# analog_channel3.net
KiCad netlist of a schematic drawn in Altium Designer
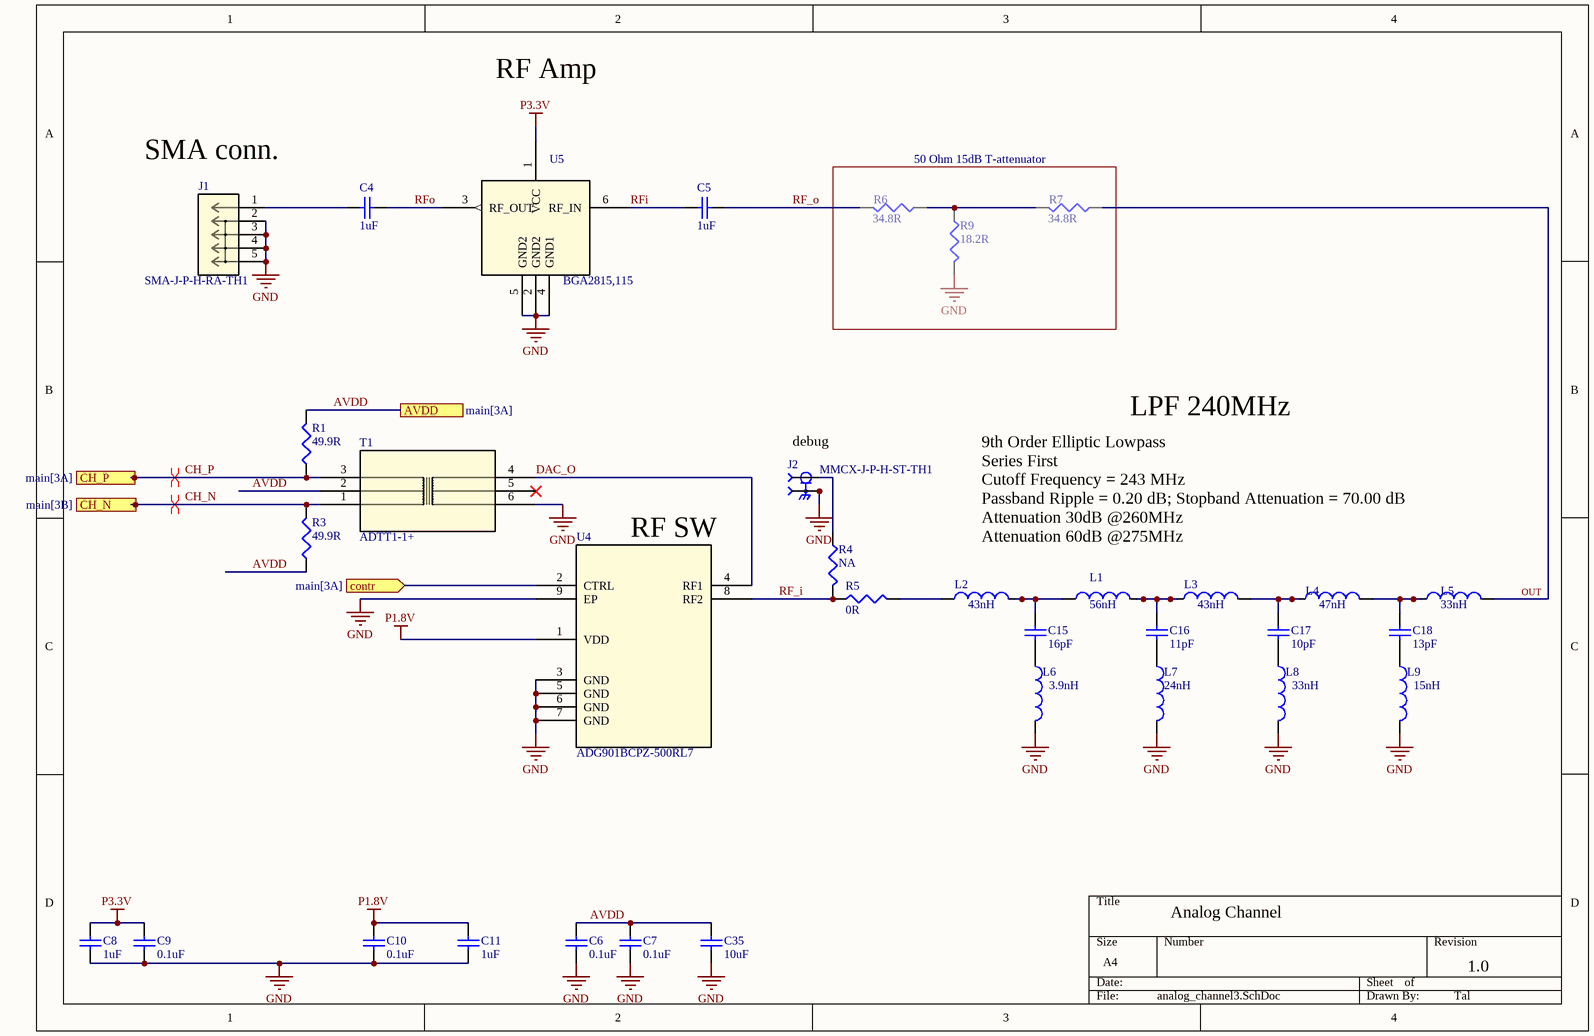
[diagram p0: analog_channel3.SchDoc]

(export (version "E")
  (design (tool "Eeschema 10.0.6"))
  (components
    (comp (ref "C4")
      (value "1uF 25V")
      (footprint "Landa_PCB:C0402")
      (description "CAP CER 1uF 25V X5R 0402")
      (fields
        (field (name "MANUFACTURER PART NUMBER") "C1005C0G1H6R8D")
        (field (name "MANUFACTURER") "TDK Corporation")
        (field (name "CAPACITANCE") "1uF")
      )
      (libsource (lib "L_SCH_C") (part "CAP CER 6.8pF 50V NP0 0402"))
    )
    (comp (ref "C5")
      (value "1uF 25V")
      (footprint "Landa_PCB:C0402")
      (description "CAP CER 1uF 25V X5R 0402")
      (fields
        (field (name "MANUFACTURER PART NUMBER") "C1005C0G1H6R8D")
        (field (name "MANUFACTURER") "TDK Corporation")
        (field (name "CAPACITANCE") "1uF")
      )
      (libsource (lib "L_SCH_C") (part "CAP CER 6.8pF 50V NP0 0402"))
    )
    (comp (ref "C6")
      (value "0.1uF 50V")
      (footprint "Landa_PCB:C0402")
      (description "CAP CER 0.1uF 50V NP0 0402")
      (fields
        (field (name "MANUFACTURER PART NUMBER") "C1005C0G1H6R8D")
        (field (name "MANUFACTURER") "TDK Corporation")
        (field (name "CAPACITANCE") "0.1uF")
      )
      (libsource (lib "L_SCH_C") (part "CAP CER 6.8pF 50V NP0 0402"))
    )
    (comp (ref "C7")
      (value "0.1uF 50V")
      (footprint "Landa_PCB:C0402")
      (description "CAP CER 0.1uF 50V NP0 0402")
      (fields
        (field (name "MANUFACTURER PART NUMBER") "C1005C0G1H6R8D")
        (field (name "MANUFACTURER") "TDK Corporation")
        (field (name "CAPACITANCE") "0.1uF")
      )
      (libsource (lib "L_SCH_C") (part "CAP CER 6.8pF 50V NP0 0402"))
    )
    (comp (ref "C8")
      (value "1uF 25V")
      (footprint "Landa_PCB:C0402")
      (description "CAP CER 1uF 25V X5R 0402")
      (fields
        (field (name "MANUFACTURER PART NUMBER") "C1005C0G1H6R8D")
        (field (name "MANUFACTURER") "TDK Corporation")
        (field (name "CAPACITANCE") "1uF")
      )
      (libsource (lib "L_SCH_C") (part "CAP CER 6.8pF 50V NP0 0402"))
    )
    (comp (ref "C9")
      (value "0.1uF 50V")
      (footprint "Landa_PCB:C0402")
      (description "CAP CER 0.1uF 50V NP0 0402")
      (fields
        (field (name "MANUFACTURER PART NUMBER") "C1005C0G1H6R8D")
        (field (name "MANUFACTURER") "TDK Corporation")
        (field (name "CAPACITANCE") "0.1uF")
      )
      (libsource (lib "L_SCH_C") (part "CAP CER 6.8pF 50V NP0 0402"))
    )
    (comp (ref "C10")
      (value "0.1uF 50V")
      (footprint "Landa_PCB:C0402")
      (description "CAP CER 0.1uF 50V NP0 0402")
      (fields
        (field (name "MANUFACTURER PART NUMBER") "C1005C0G1H6R8D")
        (field (name "MANUFACTURER") "TDK Corporation")
        (field (name "CAPACITANCE") "0.1uF")
      )
      (libsource (lib "L_SCH_C") (part "CAP CER 6.8pF 50V NP0 0402"))
    )
    (comp (ref "C11")
      (value "1uF 25V")
      (footprint "Landa_PCB:C0402")
      (description "CAP CER 1uF 25V X5R 0402")
      (fields
        (field (name "MANUFACTURER PART NUMBER") "C1005C0G1H6R8D")
        (field (name "MANUFACTURER") "TDK Corporation")
        (field (name "CAPACITANCE") "1uF")
      )
      (libsource (lib "L_SCH_C") (part "CAP CER 6.8pF 50V NP0 0402"))
    )
    (comp (ref "C15")
      (value "16pF 50V")
      (footprint "Landa_PCB:C0402")
      (description "CAP CER 16PF 50V 5% NP0 0402")
      (fields
        (field (name "MANUFACTURER") "TDK Corporation")
        (field (name "MANUFACTURER PART NUMBER") "C1005C0G1H200J")
        (field (name "CAPACITANCE") "16pF")
      )
      (libsource (lib "L_SCH_C") (part "CAP CER 20pF 50V 5% NP0 0402"))
    )
    (comp (ref "C16")
      (value "11pF 50V")
      (footprint "Landa_PCB:C0402")
      (description "CAP CER 11PF 50V 5% NP0 0402")
      (fields
        (field (name "MANUFACTURER") "TDK Corporation")
        (field (name "MANUFACTURER PART NUMBER") "C1005C0G1H200J")
        (field (name "CAPACITANCE") "11pF")
      )
      (libsource (lib "L_SCH_C") (part "CAP CER 20pF 50V 5% NP0 0402"))
    )
    (comp (ref "C17")
      (value "10pF 50V")
      (footprint "Landa_PCB:C0402")
      (description "CAP CER 10PF 50V 5% NP0 0402")
      (fields
        (field (name "MANUFACTURER") "TDK Corporation")
        (field (name "MANUFACTURER PART NUMBER") "C1005C0G1H200J")
        (field (name "CAPACITANCE") "10pF")
      )
      (libsource (lib "L_SCH_C") (part "CAP CER 20pF 50V 5% NP0 0402"))
    )
    (comp (ref "C18")
      (value "13pF 50V")
      (footprint "Landa_PCB:C0402")
      (description "CAP CER 13PF 50V 5% NP0 0402")
      (fields
        (field (name "MANUFACTURER") "TDK Corporation")
        (field (name "MANUFACTURER PART NUMBER") "C1005C0G1H200J")
        (field (name "CAPACITANCE") "13pF")
      )
      (libsource (lib "L_SCH_C") (part "CAP CER 20pF 50V 5% NP0 0402"))
    )
    (comp (ref "C35")
      (value "10uF 10V")
      (footprint "Landa_PCB:C0402")
      (description "CAP CER 10uF 10V X5R 0402")
      (fields
        (field (name "MANUFACTURER PART NUMBER") "C1005C0G1H6R8D")
        (field (name "MANUFACTURER") "TDK Corporation")
        (field (name "CAPACITANCE") "10uF")
      )
      (libsource (lib "L_SCH_C") (part "CAP CER 6.8pF 50V NP0 0402"))
    )
    (comp (ref "J1")
      (value "SMA-J-P-H-RA-TH1")
      (footprint "CONN_SMA-J-P-H-RA-TH1_SAI")
      (description "No Description Available")
      (fields (field (name "COPYRIGHT") "Copyright (C) 2023 Ultra Librarian. All rights reserved."))
      (libsource (lib "SMA-J-P-H-RA-TH1") (part "SMA-J-P-H-RA-TH1"))
    )
    (comp (ref "J2")
      (value "MMCX-J-P-H-ST-TH1")
      (footprint "SAMTEC_MMCX-J-P-H-ST-TH1")
      (description "MMCX STRAIGHT, THROUGH HOLE JACK- 50 OHM")
      (fields (field (name "MF") "Samtec"))
      (libsource (lib "MMCX-J-P-H-ST-TH1") (part "MMCX-J-P-H-ST-TH1"))
    )
    (comp (ref "L1")
      (value "56nH")
      (footprint "0402-A")
      (description "Inductor")
      (fields (field (name "PUBLISHER") "Altium Limited"))
      (libsource (lib "Miscellaneous Devices") (part "Inductor"))
    )
    (comp (ref "L2")
      (value "43nH")
      (footprint "0402-A")
      (description "Inductor")
      (fields (field (name "PUBLISHER") "Altium Limited"))
      (libsource (lib "Miscellaneous Devices") (part "Inductor"))
    )
    (comp (ref "L3")
      (value "43nH")
      (footprint "0402-A")
      (description "Inductor")
      (fields (field (name "PUBLISHER") "Altium Limited"))
      (libsource (lib "Miscellaneous Devices") (part "Inductor"))
    )
    (comp (ref "L4")
      (value "47nH")
      (footprint "0402-A")
      (description "Inductor")
      (fields (field (name "PUBLISHER") "Altium Limited"))
      (libsource (lib "Miscellaneous Devices") (part "Inductor"))
    )
    (comp (ref "L5")
      (value "33nH")
      (footprint "0402-A")
      (description "Inductor")
      (fields (field (name "PUBLISHER") "Altium Limited"))
      (libsource (lib "Miscellaneous Devices") (part "Inductor"))
    )
    (comp (ref "L6")
      (value "3.9nH")
      (footprint "0402-A")
      (description "Inductor")
      (fields (field (name "PUBLISHER") "Altium Limited"))
      (libsource (lib "Miscellaneous Devices") (part "Inductor"))
    )
    (comp (ref "L7")
      (value "24nH")
      (footprint "0402-A")
      (description "Inductor")
      (fields (field (name "PUBLISHER") "Altium Limited"))
      (libsource (lib "Miscellaneous Devices") (part "Inductor"))
    )
    (comp (ref "L8")
      (value "33nH")
      (footprint "0402-A")
      (description "Inductor")
      (fields (field (name "PUBLISHER") "Altium Limited"))
      (libsource (lib "Miscellaneous Devices") (part "Inductor"))
    )
    (comp (ref "L9")
      (value "15nH")
      (footprint "0402-A")
      (description "Inductor")
      (fields (field (name "PUBLISHER") "Altium Limited"))
      (libsource (lib "Miscellaneous Devices") (part "Inductor"))
    )
    (comp (ref "R1")
      (value "49.9R")
      (footprint "Landa_PCB:R0402")
      (description "RES 49.9 OHM 1/10W 1% 0402 SMD")
      (fields
        (field (name "MANUFACTURER PART NUMBER") "ERJ-2RKF1000X")
        (field (name "MANUFACTURER") "Panasonic Electronic Components")
      )
      (libsource (lib "L_SCH_R") (part "RES 100 OHM 1/10W 1% 0402 SMD"))
    )
    (comp (ref "R3")
      (value "49.9R")
      (footprint "Landa_PCB:R0402")
      (description "RES 49.9 OHM 1/10W 1% 0402 SMD")
      (fields
        (field (name "MANUFACTURER PART NUMBER") "ERJ-2RKF1000X")
        (field (name "MANUFACTURER") "Panasonic Electronic Components")
      )
      (libsource (lib "L_SCH_R") (part "RES 100 OHM 1/10W 1% 0402 SMD"))
    )
    (comp (ref "R4")
      (value "NA")
      (footprint "r0402")
      (description "RES 0 OHM 1/10W 1% 0402 SMD")
      (fields
        (field (name "MANUFACTURER PART NUMBER") "ERJ-2RKF1000X")
        (field (name "MANUFACTURER") "Panasonic Electronic Components")
      )
      (libsource (lib "L_SCH_R") (part "RES 100 OHM 1/10W 1% 0402 SMD"))
    )
    (comp (ref "R5")
      (value "0R")
      (footprint "r0402")
      (description "RES 0 OHM 1/10W 1% 0402 SMD")
      (fields
        (field (name "MANUFACTURER PART NUMBER") "ERJ-2RKF1000X")
        (field (name "MANUFACTURER") "Panasonic Electronic Components")
      )
      (libsource (lib "L_SCH_R") (part "RES 100 OHM 1/10W 1% 0402 SMD"))
    )
    (comp (ref "R6")
      (value "34.8R")
      (footprint "r0402")
      (description "RES 34.8 OHM 1/10W 1% 0402 SMD")
      (fields
        (field (name "MANUFACTURER PART NUMBER") "ERJ-2RKF1000X")
        (field (name "MANUFACTURER") "Panasonic Electronic Components")
      )
      (libsource (lib "L_SCH_R") (part "RES 100 OHM 1/10W 1% 0402 SMD"))
    )
    (comp (ref "R7")
      (value "34.8R")
      (footprint "r0402")
      (description "RES 34.8 OHM 1/10W 1% 0402 SMD")
      (fields
        (field (name "MANUFACTURER PART NUMBER") "ERJ-2RKF1000X")
        (field (name "MANUFACTURER") "Panasonic Electronic Components")
      )
      (libsource (lib "L_SCH_R") (part "RES 100 OHM 1/10W 1% 0402 SMD"))
    )
    (comp (ref "R9")
      (value "18.2R")
      (footprint "r0402")
      (description "RES 18.2 OHM 1/10W 1% 0402 SMD")
      (fields
        (field (name "MANUFACTURER PART NUMBER") "ERJ-2RKF1000X")
        (field (name "MANUFACTURER") "Panasonic Electronic Components")
      )
      (libsource (lib "L_SCH_R") (part "RES 100 OHM 1/10W 1% 0402 SMD"))
    )
    (comp (ref "T1")
      (value "ADTT1-1+")
      (footprint "CD542_MNC")
      (description "No Description Available")
      (fields (field (name "COPYRIGHT") "Copyright (C) 2023 Ultra Librarian. All rights reserved."))
      (libsource (lib "ADTT1-1&plus_") (part "ADTT1-1+"))
    )
    (comp (ref "U4")
      (value "ADG901BCPZ-500RL7")
      (footprint "CP_8_2_ADI")
      (description "No Description Available")
      (fields (field (name "COPYRIGHT") "Copyright (C) 2023 Ultra Librarian. All rights reserved."))
      (libsource (lib "ADG901BCPZ-500RL7") (part "ADG901BCPZ-500RL7"))
    )
    (comp (ref "U5")
      (value "BGA2815,115")
      (footprint "SOT_2815,115_NXP")
      (description "No Description Available")
      (fields (field (name "COPYRIGHT") "Copyright (C) 2023 Ultra Librarian. All rights reserved."))
      (libsource (lib "BGA2815,115") (part "BGA2815,115"))
    )
  )
  (nets
    (net (code "1") (name "/AVDD") (class "Default")
      (node (ref "C35") (pin "2") (pinfunction "2_2") (pintype "passive"))
      (node (ref "C6") (pin "2") (pinfunction "2_2") (pintype "passive"))
      (node (ref "C7") (pin "2") (pinfunction "2_2") (pintype "passive"))
      (node (ref "R1") (pin "2") (pinfunction "2_2") (pintype "passive"))
      (node (ref "R3") (pin "1") (pinfunction "1_1") (pintype "passive"))
      (node (ref "T1") (pin "2") (pinfunction "2_2") (pintype "passive"))
    )
    (net (code "2") (name "/CH_N") (class "Default")
      (node (ref "R3") (pin "2") (pinfunction "2_2") (pintype "passive"))
      (node (ref "T1") (pin "1") (pinfunction "1_1") (pintype "passive"))
    )
    (net (code "3") (name "/CH_P") (class "Default")
      (node (ref "R1") (pin "1") (pinfunction "1_1") (pintype "passive"))
      (node (ref "T1") (pin "3") (pinfunction "3_3") (pintype "passive"))
    )
    (net (code "4") (name "/DAC_O") (class "Default")
      (node (ref "T1") (pin "4") (pinfunction "4_4") (pintype "passive"))
      (node (ref "U4") (pin "4") (pinfunction "RF1_4") (pintype "passive"))
    )
    (net (code "5") (name "/OUT") (class "Default")
      (node (ref "L5") (pin "2") (pinfunction "2_2") (pintype "passive"))
      (node (ref "R7") (pin "1") (pinfunction "1_1") (pintype "passive"))
    )
    (net (code "6") (name "/RF_i") (class "Default")
      (node (ref "R4") (pin "2") (pinfunction "2_2") (pintype "passive"))
      (node (ref "R5") (pin "1") (pinfunction "1_1") (pintype "passive"))
      (node (ref "U4") (pin "8") (pinfunction "RF2_8") (pintype "passive"))
    )
    (net (code "7") (name "/RF_o") (class "Default")
      (node (ref "C5") (pin "2") (pinfunction "2_2") (pintype "passive"))
      (node (ref "R6") (pin "2") (pinfunction "2_2") (pintype "passive"))
    )
    (net (code "8") (name "/RFi") (class "Default")
      (node (ref "C5") (pin "1") (pinfunction "1_1") (pintype "passive"))
      (node (ref "U5") (pin "6") (pinfunction "RF_IN_6") (pintype "passive"))
    )
    (net (code "9") (name "/RFo") (class "Default")
      (node (ref "C4") (pin "2") (pinfunction "2_2") (pintype "passive"))
      (node (ref "U5") (pin "3") (pinfunction "RF_OUT_3") (pintype "output"))
    )
    (net (code "10") (name "/contr") (class "Default")
      (node (ref "U4") (pin "2") (pinfunction "CTRL_2") (pintype "passive"))
    )
    (net (code "11") (name "GND") (class "Default")
      (node (ref "C10") (pin "1") (pinfunction "1_1") (pintype "passive"))
      (node (ref "C11") (pin "1") (pinfunction "1_1") (pintype "passive"))
      (node (ref "C35") (pin "1") (pinfunction "1_1") (pintype "passive"))
      (node (ref "C6") (pin "1") (pinfunction "1_1") (pintype "passive"))
      (node (ref "C7") (pin "1") (pinfunction "1_1") (pintype "passive"))
      (node (ref "C8") (pin "1") (pinfunction "1_1") (pintype "passive"))
      (node (ref "C9") (pin "1") (pinfunction "1_1") (pintype "passive"))
      (node (ref "J1") (pin "2") (pinfunction "2_2") (pintype "passive"))
      (node (ref "J1") (pin "3") (pinfunction "3_3") (pintype "passive"))
      (node (ref "J1") (pin "4") (pinfunction "4_4") (pintype "passive"))
      (node (ref "J1") (pin "5") (pinfunction "5_5") (pintype "passive"))
      (node (ref "J2") (pin "S1") (pinfunction "2_S1") (pintype "passive"))
      (node (ref "J2") (pin "S2") (pinfunction "2_S2") (pintype "passive"))
      (node (ref "J2") (pin "S3") (pinfunction "2_S3") (pintype "passive"))
      (node (ref "J2") (pin "S4") (pinfunction "2_S4") (pintype "passive"))
      (node (ref "L6") (pin "2") (pinfunction "2_2") (pintype "passive"))
      (node (ref "L7") (pin "2") (pinfunction "2_2") (pintype "passive"))
      (node (ref "L8") (pin "2") (pinfunction "2_2") (pintype "passive"))
      (node (ref "L9") (pin "2") (pinfunction "2_2") (pintype "passive"))
      (node (ref "R9") (pin "2") (pinfunction "2_2") (pintype "passive"))
      (node (ref "T1") (pin "6") (pinfunction "6_6") (pintype "passive"))
      (node (ref "U4") (pin "3") (pinfunction "GND_3") (pintype "passive"))
      (node (ref "U4") (pin "5") (pinfunction "GND_5") (pintype "passive"))
      (node (ref "U4") (pin "6") (pinfunction "GND_6") (pintype "passive"))
      (node (ref "U4") (pin "7") (pinfunction "GND_7") (pintype "passive"))
      (node (ref "U4") (pin "9") (pinfunction "EP_9") (pintype "passive"))
      (node (ref "U5") (pin "2") (pinfunction "GND2_2") (pintype "passive"))
      (node (ref "U5") (pin "4") (pinfunction "GND1_4") (pintype "passive"))
      (node (ref "U5") (pin "5") (pinfunction "GND2_5") (pintype "passive"))
    )
    (net (code "12") (name "Net-(C4-Pad1)") (class "Default")
      (node (ref "C4") (pin "1") (pinfunction "1_1") (pintype "passive"))
      (node (ref "J1") (pin "1") (pinfunction "1_1") (pintype "passive"))
    )
    (net (code "13") (name "Net-(C15-Pad1)") (class "Default")
      (node (ref "C15") (pin "1") (pinfunction "1_1") (pintype "passive"))
      (node (ref "L1") (pin "1") (pinfunction "1_1") (pintype "passive"))
      (node (ref "L2") (pin "2") (pinfunction "2_2") (pintype "passive"))
    )
    (net (code "14") (name "Net-(C15-Pad2)") (class "Default")
      (node (ref "C15") (pin "2") (pinfunction "2_2") (pintype "passive"))
      (node (ref "L6") (pin "1") (pinfunction "1_1") (pintype "passive"))
    )
    (net (code "15") (name "Net-(C16-Pad1)") (class "Default")
      (node (ref "C16") (pin "1") (pinfunction "1_1") (pintype "passive"))
      (node (ref "L1") (pin "2") (pinfunction "2_2") (pintype "passive"))
      (node (ref "L3") (pin "1") (pinfunction "1_1") (pintype "passive"))
    )
    (net (code "16") (name "Net-(C16-Pad2)") (class "Default")
      (node (ref "C16") (pin "2") (pinfunction "2_2") (pintype "passive"))
      (node (ref "L7") (pin "1") (pinfunction "1_1") (pintype "passive"))
    )
    (net (code "17") (name "Net-(C17-Pad1)") (class "Default")
      (node (ref "C17") (pin "1") (pinfunction "1_1") (pintype "passive"))
      (node (ref "L3") (pin "2") (pinfunction "2_2") (pintype "passive"))
      (node (ref "L4") (pin "1") (pinfunction "1_1") (pintype "passive"))
    )
    (net (code "18") (name "Net-(C17-Pad2)") (class "Default")
      (node (ref "C17") (pin "2") (pinfunction "2_2") (pintype "passive"))
      (node (ref "L8") (pin "1") (pinfunction "1_1") (pintype "passive"))
    )
    (net (code "19") (name "Net-(C18-Pad1)") (class "Default")
      (node (ref "C18") (pin "1") (pinfunction "1_1") (pintype "passive"))
      (node (ref "L4") (pin "2") (pinfunction "2_2") (pintype "passive"))
      (node (ref "L5") (pin "1") (pinfunction "1_1") (pintype "passive"))
    )
    (net (code "20") (name "Net-(C18-Pad2)") (class "Default")
      (node (ref "C18") (pin "2") (pinfunction "2_2") (pintype "passive"))
      (node (ref "L9") (pin "1") (pinfunction "1_1") (pintype "passive"))
    )
    (net (code "21") (name "Net-(J2-Pad1)") (class "Default")
      (node (ref "J2") (pin "1") (pinfunction "1_1") (pintype "passive"))
      (node (ref "R4") (pin "1") (pinfunction "1_1") (pintype "passive"))
    )
    (net (code "22") (name "Net-(L2-Pad1)") (class "Default")
      (node (ref "L2") (pin "1") (pinfunction "1_1") (pintype "passive"))
      (node (ref "R5") (pin "2") (pinfunction "2_2") (pintype "passive"))
    )
    (net (code "23") (name "Net-(R6-Pad1)") (class "Default")
      (node (ref "R6") (pin "1") (pinfunction "1_1") (pintype "passive"))
      (node (ref "R7") (pin "2") (pinfunction "2_2") (pintype "passive"))
      (node (ref "R9") (pin "1") (pinfunction "1_1") (pintype "passive"))
    )
    (net (code "24") (name "P1.8V") (class "Default")
      (node (ref "C10") (pin "2") (pinfunction "2_2") (pintype "passive"))
      (node (ref "C11") (pin "2") (pinfunction "2_2") (pintype "passive"))
      (node (ref "U4") (pin "1") (pinfunction "VDD_1") (pintype "power_in"))
    )
    (net (code "25") (name "P3.3V") (class "Default")
      (node (ref "C8") (pin "2") (pinfunction "2_2") (pintype "passive"))
      (node (ref "C9") (pin "2") (pinfunction "2_2") (pintype "passive"))
      (node (ref "U5") (pin "1") (pinfunction "VCC_1") (pintype "power_in"))
    )
    (net (code "26") (name "unconnected-(T1-Pad5)") (class "Default")
      (node (ref "T1") (pin "5") (pinfunction "5_5") (pintype "passive+no_connect"))
    )
  )
)
